# design.net
KiCad netlist of a schematic drawn in EasyEDA Pro
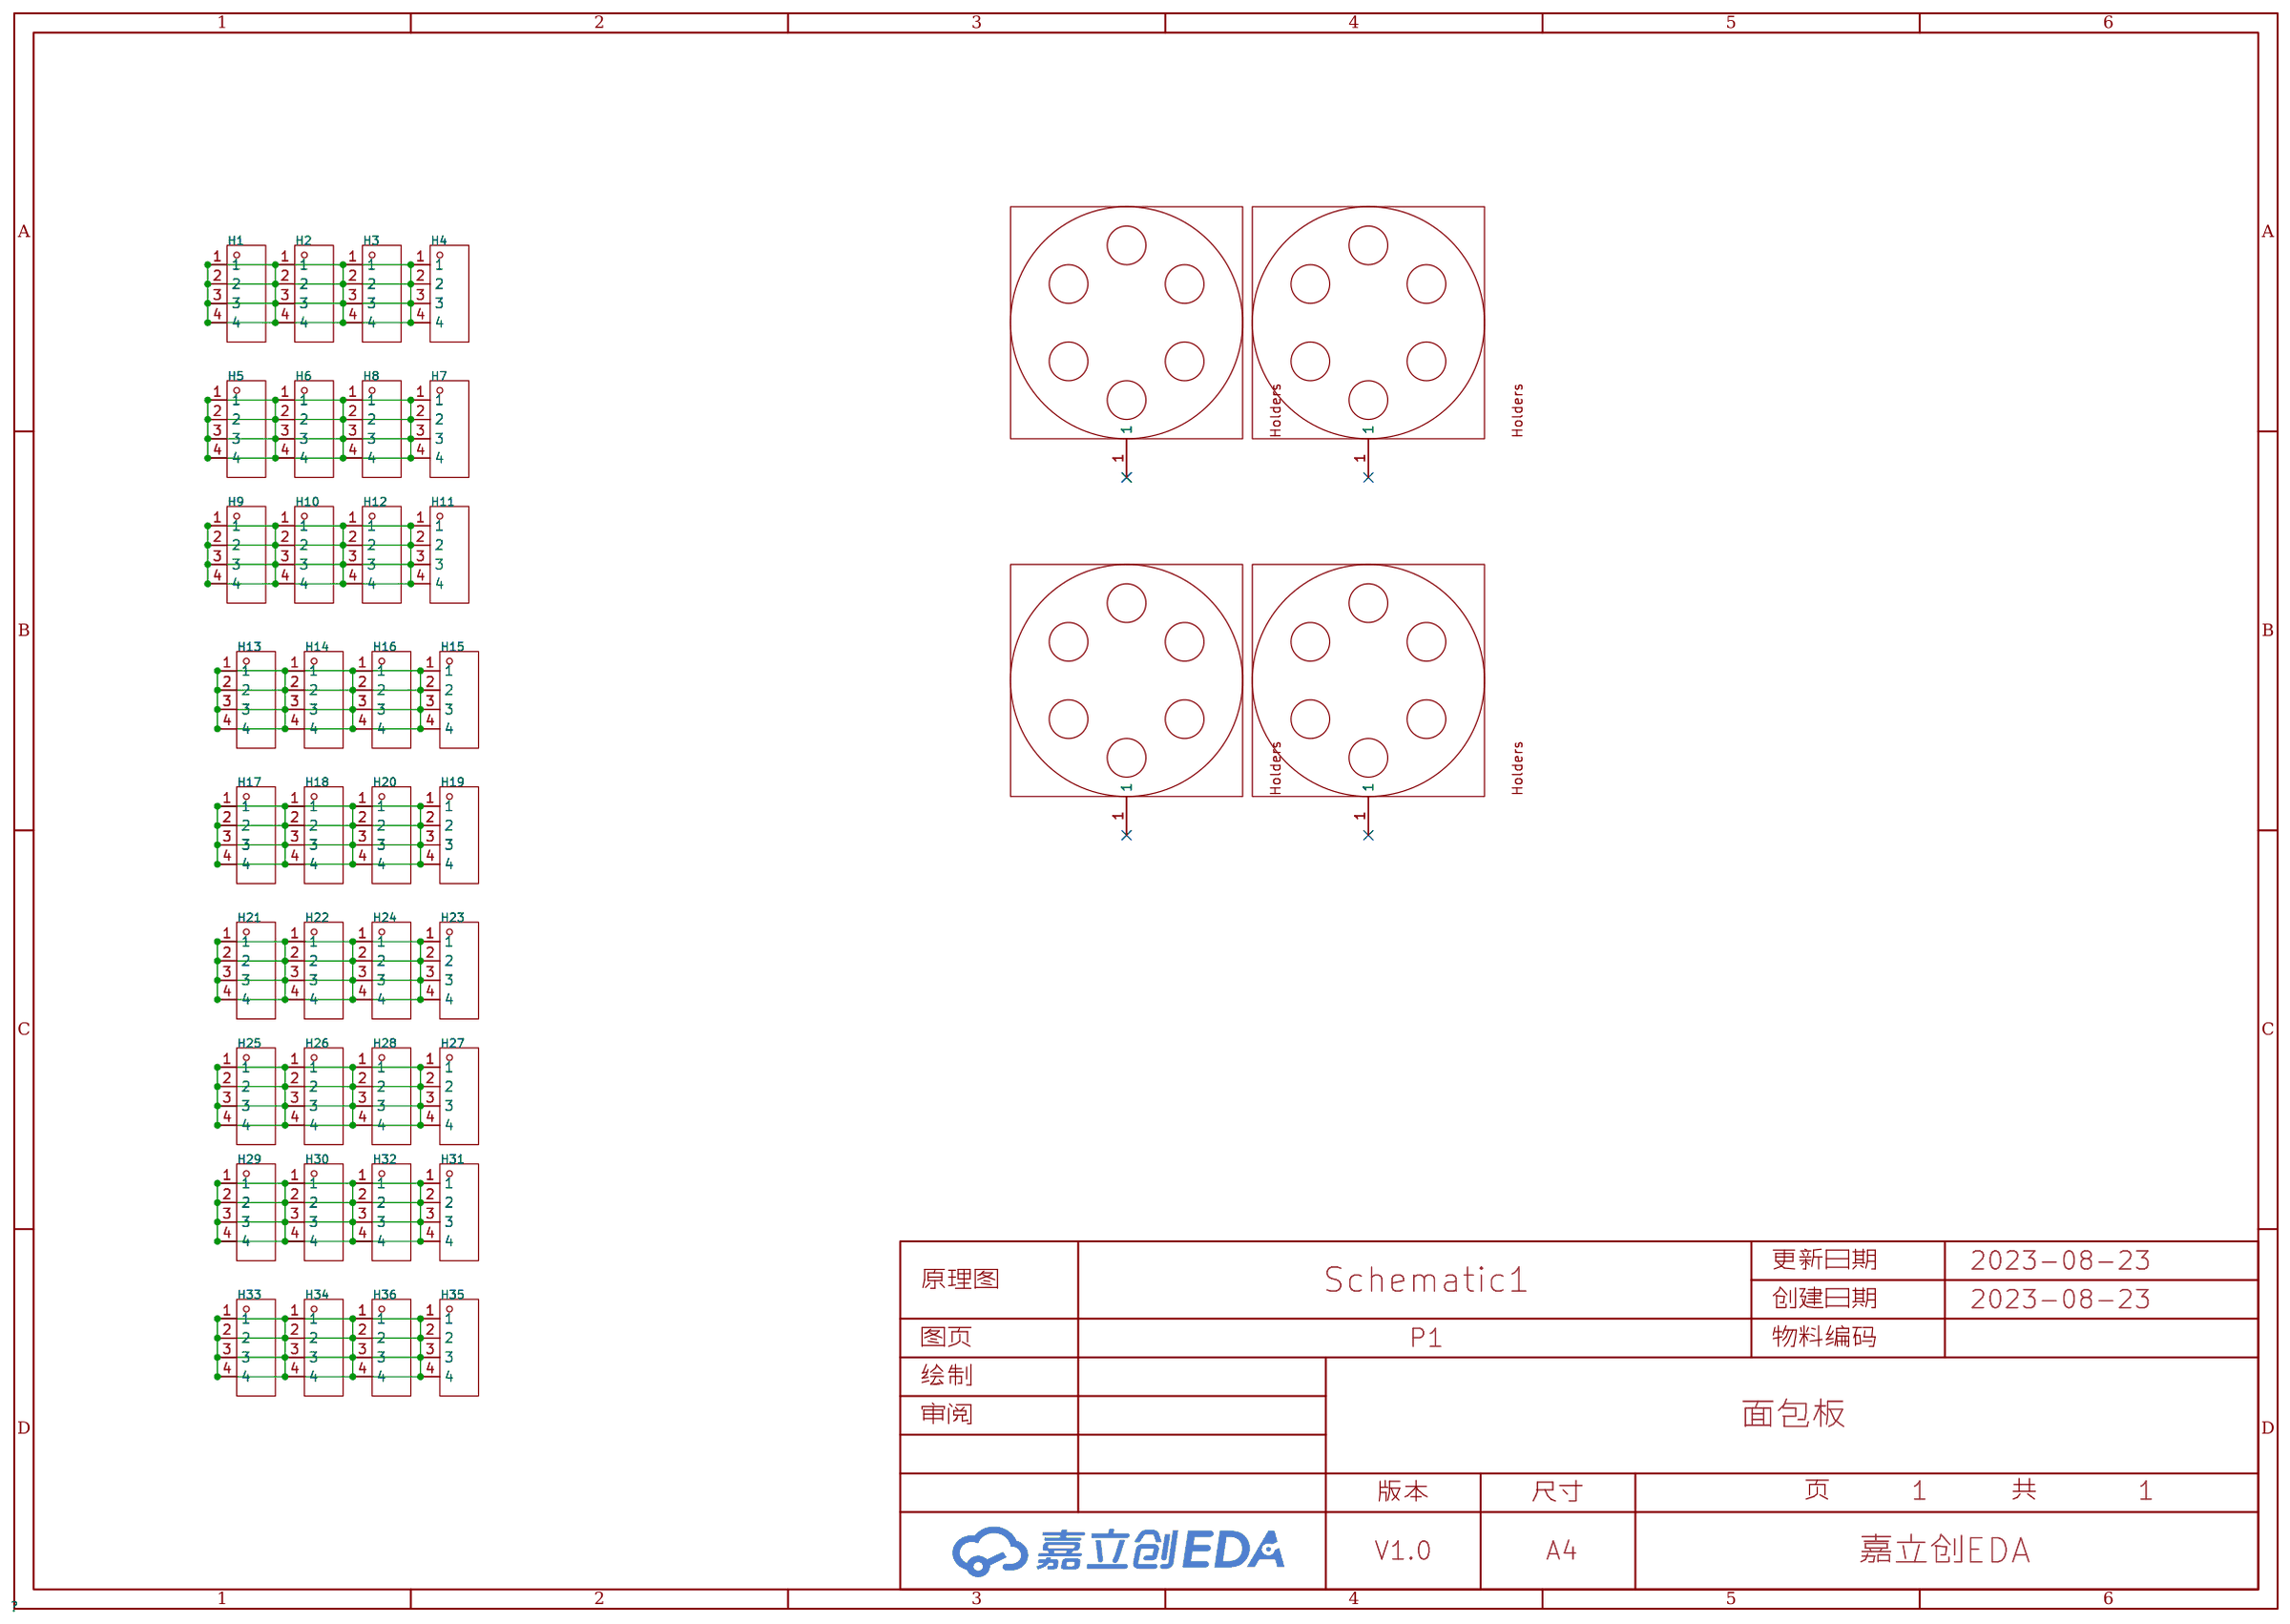
[diagram p0: schematic sheet]

(export (version "E")
  (design (tool "Eeschema 10.0.6"))
  (components
    (comp (ref "H1")
      (value "PZ254V-11-04P")
      (footprint "easyedapro:HDR-TH_4P-P2.54-V-M")
      (fields (field (name "Manufacturer") "XFCN(兴飞)"))
      (libsource (lib "easyedapro") (part "PZ254V-11-04P_C2691448"))
    )
    (comp (ref "H2")
      (value "PZ254V-11-04P")
      (footprint "easyedapro:HDR-TH_4P-P2.54-V-M")
      (fields (field (name "Manufacturer") "XFCN(兴飞)"))
      (libsource (lib "easyedapro") (part "PZ254V-11-04P_C2691448"))
    )
    (comp (ref "H3")
      (value "PZ254V-11-04P")
      (footprint "easyedapro:HDR-TH_4P-P2.54-V-M")
      (fields (field (name "Manufacturer") "XFCN(兴飞)"))
      (libsource (lib "easyedapro") (part "PZ254V-11-04P_C2691448"))
    )
    (comp (ref "H4")
      (value "PZ254V-11-04P")
      (footprint "easyedapro:HDR-TH_4P-P2.54-V-M")
      (fields (field (name "Manufacturer") "XFCN(兴飞)"))
      (libsource (lib "easyedapro") (part "PZ254V-11-04P_C2691448"))
    )
    (comp (ref "H5")
      (value "PZ254V-11-04P")
      (footprint "easyedapro:HDR-TH_4P-P2.54-V-M")
      (fields (field (name "Manufacturer") "XFCN(兴飞)"))
      (libsource (lib "easyedapro") (part "PZ254V-11-04P_C2691448"))
    )
    (comp (ref "H6")
      (value "PZ254V-11-04P")
      (footprint "easyedapro:HDR-TH_4P-P2.54-V-M")
      (fields (field (name "Manufacturer") "XFCN(兴飞)"))
      (libsource (lib "easyedapro") (part "PZ254V-11-04P_C2691448"))
    )
    (comp (ref "H7")
      (value "PZ254V-11-04P")
      (footprint "easyedapro:HDR-TH_4P-P2.54-V-M")
      (fields (field (name "Manufacturer") "XFCN(兴飞)"))
      (libsource (lib "easyedapro") (part "PZ254V-11-04P_C2691448"))
    )
    (comp (ref "H8")
      (value "PZ254V-11-04P")
      (footprint "easyedapro:HDR-TH_4P-P2.54-V-M")
      (fields (field (name "Manufacturer") "XFCN(兴飞)"))
      (libsource (lib "easyedapro") (part "PZ254V-11-04P_C2691448"))
    )
    (comp (ref "H9")
      (value "PZ254V-11-04P")
      (footprint "easyedapro:HDR-TH_4P-P2.54-V-M")
      (fields (field (name "Manufacturer") "XFCN(兴飞)"))
      (libsource (lib "easyedapro") (part "PZ254V-11-04P_C2691448"))
    )
    (comp (ref "H10")
      (value "PZ254V-11-04P")
      (footprint "easyedapro:HDR-TH_4P-P2.54-V-M")
      (fields (field (name "Manufacturer") "XFCN(兴飞)"))
      (libsource (lib "easyedapro") (part "PZ254V-11-04P_C2691448"))
    )
    (comp (ref "H11")
      (value "PZ254V-11-04P")
      (footprint "easyedapro:HDR-TH_4P-P2.54-V-M")
      (fields (field (name "Manufacturer") "XFCN(兴飞)"))
      (libsource (lib "easyedapro") (part "PZ254V-11-04P_C2691448"))
    )
    (comp (ref "H12")
      (value "PZ254V-11-04P")
      (footprint "easyedapro:HDR-TH_4P-P2.54-V-M")
      (fields (field (name "Manufacturer") "XFCN(兴飞)"))
      (libsource (lib "easyedapro") (part "PZ254V-11-04P_C2691448"))
    )
    (comp (ref "H13")
      (value "PZ254V-11-04P")
      (footprint "easyedapro:HDR-TH_4P-P2.54-V-M")
      (fields (field (name "Manufacturer") "XFCN(兴飞)"))
      (libsource (lib "easyedapro") (part "PZ254V-11-04P_C2691448"))
    )
    (comp (ref "H14")
      (value "PZ254V-11-04P")
      (footprint "easyedapro:HDR-TH_4P-P2.54-V-M")
      (fields (field (name "Manufacturer") "XFCN(兴飞)"))
      (libsource (lib "easyedapro") (part "PZ254V-11-04P_C2691448"))
    )
    (comp (ref "H15")
      (value "PZ254V-11-04P")
      (footprint "easyedapro:HDR-TH_4P-P2.54-V-M")
      (fields (field (name "Manufacturer") "XFCN(兴飞)"))
      (libsource (lib "easyedapro") (part "PZ254V-11-04P_C2691448"))
    )
    (comp (ref "H16")
      (value "PZ254V-11-04P")
      (footprint "easyedapro:HDR-TH_4P-P2.54-V-M")
      (fields (field (name "Manufacturer") "XFCN(兴飞)"))
      (libsource (lib "easyedapro") (part "PZ254V-11-04P_C2691448"))
    )
    (comp (ref "H17")
      (value "PZ254V-11-04P")
      (footprint "easyedapro:HDR-TH_4P-P2.54-V-M")
      (fields (field (name "Manufacturer") "XFCN(兴飞)"))
      (libsource (lib "easyedapro") (part "PZ254V-11-04P_C2691448"))
    )
    (comp (ref "H18")
      (value "PZ254V-11-04P")
      (footprint "easyedapro:HDR-TH_4P-P2.54-V-M")
      (fields (field (name "Manufacturer") "XFCN(兴飞)"))
      (libsource (lib "easyedapro") (part "PZ254V-11-04P_C2691448"))
    )
    (comp (ref "H19")
      (value "PZ254V-11-04P")
      (footprint "easyedapro:HDR-TH_4P-P2.54-V-M")
      (fields (field (name "Manufacturer") "XFCN(兴飞)"))
      (libsource (lib "easyedapro") (part "PZ254V-11-04P_C2691448"))
    )
    (comp (ref "H20")
      (value "PZ254V-11-04P")
      (footprint "easyedapro:HDR-TH_4P-P2.54-V-M")
      (fields (field (name "Manufacturer") "XFCN(兴飞)"))
      (libsource (lib "easyedapro") (part "PZ254V-11-04P_C2691448"))
    )
    (comp (ref "H21")
      (value "PZ254V-11-04P")
      (footprint "easyedapro:HDR-TH_4P-P2.54-V-M")
      (fields (field (name "Manufacturer") "XFCN(兴飞)"))
      (libsource (lib "easyedapro") (part "PZ254V-11-04P_C2691448"))
    )
    (comp (ref "H22")
      (value "PZ254V-11-04P")
      (footprint "easyedapro:HDR-TH_4P-P2.54-V-M")
      (fields (field (name "Manufacturer") "XFCN(兴飞)"))
      (libsource (lib "easyedapro") (part "PZ254V-11-04P_C2691448"))
    )
    (comp (ref "H23")
      (value "PZ254V-11-04P")
      (footprint "easyedapro:HDR-TH_4P-P2.54-V-M")
      (fields (field (name "Manufacturer") "XFCN(兴飞)"))
      (libsource (lib "easyedapro") (part "PZ254V-11-04P_C2691448"))
    )
    (comp (ref "H24")
      (value "PZ254V-11-04P")
      (footprint "easyedapro:HDR-TH_4P-P2.54-V-M")
      (fields (field (name "Manufacturer") "XFCN(兴飞)"))
      (libsource (lib "easyedapro") (part "PZ254V-11-04P_C2691448"))
    )
    (comp (ref "H25")
      (value "PZ254V-11-04P")
      (footprint "easyedapro:HDR-TH_4P-P2.54-V-M")
      (fields (field (name "Manufacturer") "XFCN(兴飞)"))
      (libsource (lib "easyedapro") (part "PZ254V-11-04P_C2691448"))
    )
    (comp (ref "H26")
      (value "PZ254V-11-04P")
      (footprint "easyedapro:HDR-TH_4P-P2.54-V-M")
      (fields (field (name "Manufacturer") "XFCN(兴飞)"))
      (libsource (lib "easyedapro") (part "PZ254V-11-04P_C2691448"))
    )
    (comp (ref "H27")
      (value "PZ254V-11-04P")
      (footprint "easyedapro:HDR-TH_4P-P2.54-V-M")
      (fields (field (name "Manufacturer") "XFCN(兴飞)"))
      (libsource (lib "easyedapro") (part "PZ254V-11-04P_C2691448"))
    )
    (comp (ref "H28")
      (value "PZ254V-11-04P")
      (footprint "easyedapro:HDR-TH_4P-P2.54-V-M")
      (fields (field (name "Manufacturer") "XFCN(兴飞)"))
      (libsource (lib "easyedapro") (part "PZ254V-11-04P_C2691448"))
    )
    (comp (ref "H29")
      (value "PZ254V-11-04P")
      (footprint "easyedapro:HDR-TH_4P-P2.54-V-M")
      (fields (field (name "Manufacturer") "XFCN(兴飞)"))
      (libsource (lib "easyedapro") (part "PZ254V-11-04P_C2691448"))
    )
    (comp (ref "H30")
      (value "PZ254V-11-04P")
      (footprint "easyedapro:HDR-TH_4P-P2.54-V-M")
      (fields (field (name "Manufacturer") "XFCN(兴飞)"))
      (libsource (lib "easyedapro") (part "PZ254V-11-04P_C2691448"))
    )
    (comp (ref "H31")
      (value "PZ254V-11-04P")
      (footprint "easyedapro:HDR-TH_4P-P2.54-V-M")
      (fields (field (name "Manufacturer") "XFCN(兴飞)"))
      (libsource (lib "easyedapro") (part "PZ254V-11-04P_C2691448"))
    )
    (comp (ref "H32")
      (value "PZ254V-11-04P")
      (footprint "easyedapro:HDR-TH_4P-P2.54-V-M")
      (fields (field (name "Manufacturer") "XFCN(兴飞)"))
      (libsource (lib "easyedapro") (part "PZ254V-11-04P_C2691448"))
    )
    (comp (ref "H33")
      (value "PZ254V-11-04P")
      (footprint "easyedapro:HDR-TH_4P-P2.54-V-M")
      (fields (field (name "Manufacturer") "XFCN(兴飞)"))
      (libsource (lib "easyedapro") (part "PZ254V-11-04P_C2691448"))
    )
    (comp (ref "H34")
      (value "PZ254V-11-04P")
      (footprint "easyedapro:HDR-TH_4P-P2.54-V-M")
      (fields (field (name "Manufacturer") "XFCN(兴飞)"))
      (libsource (lib "easyedapro") (part "PZ254V-11-04P_C2691448"))
    )
    (comp (ref "H35")
      (value "PZ254V-11-04P")
      (footprint "easyedapro:HDR-TH_4P-P2.54-V-M")
      (fields (field (name "Manufacturer") "XFCN(兴飞)"))
      (libsource (lib "easyedapro") (part "PZ254V-11-04P_C2691448"))
    )
    (comp (ref "H36")
      (value "PZ254V-11-04P")
      (footprint "easyedapro:HDR-TH_4P-P2.54-V-M")
      (fields (field (name "Manufacturer") "XFCN(兴飞)"))
      (libsource (lib "easyedapro") (part "PZ254V-11-04P_C2691448"))
    )
    (comp (ref "J1")
      (value "~")
      (footprint "easyedapro:DEMO板安装孔")
      (libsource (lib "easyedapro") (part "螺孔_3.1X6MM"))
    )
    (comp (ref "J2")
      (value "~")
      (footprint "easyedapro:DEMO板安装孔")
      (libsource (lib "easyedapro") (part "螺孔_3.1X6MM"))
    )
    (comp (ref "J3")
      (value "~")
      (footprint "easyedapro:DEMO板安装孔")
      (libsource (lib "easyedapro") (part "螺孔_3.1X6MM"))
    )
    (comp (ref "J4")
      (value "~")
      (footprint "easyedapro:DEMO板安装孔")
      (libsource (lib "easyedapro") (part "螺孔_3.1X6MM"))
    )
  )
  (nets
    (net (code "1") (name "Net-(H1-Pad1)") (class "Default")
      (node (ref "H1") (pin "1") (pinfunction "1_1") (pintype "input"))
      (node (ref "H1") (pin "2") (pinfunction "2_2") (pintype "input"))
      (node (ref "H1") (pin "3") (pinfunction "3_3") (pintype "input"))
      (node (ref "H1") (pin "4") (pinfunction "4_4") (pintype "input"))
      (node (ref "H2") (pin "1") (pinfunction "1_1") (pintype "input"))
      (node (ref "H2") (pin "2") (pinfunction "2_2") (pintype "input"))
      (node (ref "H2") (pin "3") (pinfunction "3_3") (pintype "input"))
      (node (ref "H2") (pin "4") (pinfunction "4_4") (pintype "input"))
      (node (ref "H3") (pin "1") (pinfunction "1_1") (pintype "input"))
      (node (ref "H3") (pin "2") (pinfunction "2_2") (pintype "input"))
      (node (ref "H3") (pin "3") (pinfunction "3_3") (pintype "input"))
      (node (ref "H3") (pin "4") (pinfunction "4_4") (pintype "input"))
      (node (ref "H4") (pin "1") (pinfunction "1_1") (pintype "input"))
      (node (ref "H4") (pin "2") (pinfunction "2_2") (pintype "input"))
      (node (ref "H4") (pin "3") (pinfunction "3_3") (pintype "input"))
      (node (ref "H4") (pin "4") (pinfunction "4_4") (pintype "input"))
    )
    (net (code "2") (name "Net-(H5-Pad1)") (class "Default")
      (node (ref "H5") (pin "1") (pinfunction "1_1") (pintype "input"))
      (node (ref "H5") (pin "2") (pinfunction "2_2") (pintype "input"))
      (node (ref "H5") (pin "3") (pinfunction "3_3") (pintype "input"))
      (node (ref "H5") (pin "4") (pinfunction "4_4") (pintype "input"))
      (node (ref "H6") (pin "1") (pinfunction "1_1") (pintype "input"))
      (node (ref "H6") (pin "2") (pinfunction "2_2") (pintype "input"))
      (node (ref "H6") (pin "3") (pinfunction "3_3") (pintype "input"))
      (node (ref "H6") (pin "4") (pinfunction "4_4") (pintype "input"))
      (node (ref "H7") (pin "1") (pinfunction "1_1") (pintype "input"))
      (node (ref "H7") (pin "2") (pinfunction "2_2") (pintype "input"))
      (node (ref "H7") (pin "3") (pinfunction "3_3") (pintype "input"))
      (node (ref "H7") (pin "4") (pinfunction "4_4") (pintype "input"))
      (node (ref "H8") (pin "1") (pinfunction "1_1") (pintype "input"))
      (node (ref "H8") (pin "2") (pinfunction "2_2") (pintype "input"))
      (node (ref "H8") (pin "3") (pinfunction "3_3") (pintype "input"))
      (node (ref "H8") (pin "4") (pinfunction "4_4") (pintype "input"))
    )
    (net (code "3") (name "Net-(H10-Pad1)") (class "Default")
      (node (ref "H10") (pin "1") (pinfunction "1_1") (pintype "input"))
      (node (ref "H10") (pin "2") (pinfunction "2_2") (pintype "input"))
      (node (ref "H10") (pin "3") (pinfunction "3_3") (pintype "input"))
      (node (ref "H10") (pin "4") (pinfunction "4_4") (pintype "input"))
      (node (ref "H11") (pin "1") (pinfunction "1_1") (pintype "input"))
      (node (ref "H11") (pin "2") (pinfunction "2_2") (pintype "input"))
      (node (ref "H11") (pin "3") (pinfunction "3_3") (pintype "input"))
      (node (ref "H11") (pin "4") (pinfunction "4_4") (pintype "input"))
      (node (ref "H12") (pin "1") (pinfunction "1_1") (pintype "input"))
      (node (ref "H12") (pin "2") (pinfunction "2_2") (pintype "input"))
      (node (ref "H12") (pin "3") (pinfunction "3_3") (pintype "input"))
      (node (ref "H12") (pin "4") (pinfunction "4_4") (pintype "input"))
      (node (ref "H9") (pin "1") (pinfunction "1_1") (pintype "input"))
      (node (ref "H9") (pin "2") (pinfunction "2_2") (pintype "input"))
      (node (ref "H9") (pin "3") (pinfunction "3_3") (pintype "input"))
      (node (ref "H9") (pin "4") (pinfunction "4_4") (pintype "input"))
    )
    (net (code "4") (name "Net-(H13-Pad1)") (class "Default")
      (node (ref "H13") (pin "1") (pinfunction "1_1") (pintype "input"))
      (node (ref "H13") (pin "2") (pinfunction "2_2") (pintype "input"))
      (node (ref "H13") (pin "3") (pinfunction "3_3") (pintype "input"))
      (node (ref "H13") (pin "4") (pinfunction "4_4") (pintype "input"))
      (node (ref "H14") (pin "1") (pinfunction "1_1") (pintype "input"))
      (node (ref "H14") (pin "2") (pinfunction "2_2") (pintype "input"))
      (node (ref "H14") (pin "3") (pinfunction "3_3") (pintype "input"))
      (node (ref "H14") (pin "4") (pinfunction "4_4") (pintype "input"))
      (node (ref "H15") (pin "1") (pinfunction "1_1") (pintype "input"))
      (node (ref "H15") (pin "2") (pinfunction "2_2") (pintype "input"))
      (node (ref "H15") (pin "3") (pinfunction "3_3") (pintype "input"))
      (node (ref "H15") (pin "4") (pinfunction "4_4") (pintype "input"))
      (node (ref "H16") (pin "1") (pinfunction "1_1") (pintype "input"))
      (node (ref "H16") (pin "2") (pinfunction "2_2") (pintype "input"))
      (node (ref "H16") (pin "3") (pinfunction "3_3") (pintype "input"))
      (node (ref "H16") (pin "4") (pinfunction "4_4") (pintype "input"))
    )
    (net (code "5") (name "Net-(H17-Pad1)") (class "Default")
      (node (ref "H17") (pin "1") (pinfunction "1_1") (pintype "input"))
      (node (ref "H17") (pin "2") (pinfunction "2_2") (pintype "input"))
      (node (ref "H17") (pin "3") (pinfunction "3_3") (pintype "input"))
      (node (ref "H17") (pin "4") (pinfunction "4_4") (pintype "input"))
      (node (ref "H18") (pin "1") (pinfunction "1_1") (pintype "input"))
      (node (ref "H18") (pin "2") (pinfunction "2_2") (pintype "input"))
      (node (ref "H18") (pin "3") (pinfunction "3_3") (pintype "input"))
      (node (ref "H18") (pin "4") (pinfunction "4_4") (pintype "input"))
      (node (ref "H19") (pin "1") (pinfunction "1_1") (pintype "input"))
      (node (ref "H19") (pin "2") (pinfunction "2_2") (pintype "input"))
      (node (ref "H19") (pin "3") (pinfunction "3_3") (pintype "input"))
      (node (ref "H19") (pin "4") (pinfunction "4_4") (pintype "input"))
      (node (ref "H20") (pin "1") (pinfunction "1_1") (pintype "input"))
      (node (ref "H20") (pin "2") (pinfunction "2_2") (pintype "input"))
      (node (ref "H20") (pin "3") (pinfunction "3_3") (pintype "input"))
      (node (ref "H20") (pin "4") (pinfunction "4_4") (pintype "input"))
    )
    (net (code "6") (name "Net-(H21-Pad1)") (class "Default")
      (node (ref "H21") (pin "1") (pinfunction "1_1") (pintype "input"))
      (node (ref "H21") (pin "2") (pinfunction "2_2") (pintype "input"))
      (node (ref "H21") (pin "3") (pinfunction "3_3") (pintype "input"))
      (node (ref "H21") (pin "4") (pinfunction "4_4") (pintype "input"))
      (node (ref "H22") (pin "1") (pinfunction "1_1") (pintype "input"))
      (node (ref "H22") (pin "2") (pinfunction "2_2") (pintype "input"))
      (node (ref "H22") (pin "3") (pinfunction "3_3") (pintype "input"))
      (node (ref "H22") (pin "4") (pinfunction "4_4") (pintype "input"))
      (node (ref "H23") (pin "1") (pinfunction "1_1") (pintype "input"))
      (node (ref "H23") (pin "2") (pinfunction "2_2") (pintype "input"))
      (node (ref "H23") (pin "3") (pinfunction "3_3") (pintype "input"))
      (node (ref "H23") (pin "4") (pinfunction "4_4") (pintype "input"))
      (node (ref "H24") (pin "1") (pinfunction "1_1") (pintype "input"))
      (node (ref "H24") (pin "2") (pinfunction "2_2") (pintype "input"))
      (node (ref "H24") (pin "3") (pinfunction "3_3") (pintype "input"))
      (node (ref "H24") (pin "4") (pinfunction "4_4") (pintype "input"))
    )
    (net (code "7") (name "Net-(H25-Pad1)") (class "Default")
      (node (ref "H25") (pin "1") (pinfunction "1_1") (pintype "input"))
      (node (ref "H25") (pin "2") (pinfunction "2_2") (pintype "input"))
      (node (ref "H25") (pin "3") (pinfunction "3_3") (pintype "input"))
      (node (ref "H25") (pin "4") (pinfunction "4_4") (pintype "input"))
      (node (ref "H26") (pin "1") (pinfunction "1_1") (pintype "input"))
      (node (ref "H26") (pin "2") (pinfunction "2_2") (pintype "input"))
      (node (ref "H26") (pin "3") (pinfunction "3_3") (pintype "input"))
      (node (ref "H26") (pin "4") (pinfunction "4_4") (pintype "input"))
      (node (ref "H27") (pin "1") (pinfunction "1_1") (pintype "input"))
      (node (ref "H27") (pin "2") (pinfunction "2_2") (pintype "input"))
      (node (ref "H27") (pin "3") (pinfunction "3_3") (pintype "input"))
      (node (ref "H27") (pin "4") (pinfunction "4_4") (pintype "input"))
      (node (ref "H28") (pin "1") (pinfunction "1_1") (pintype "input"))
      (node (ref "H28") (pin "2") (pinfunction "2_2") (pintype "input"))
      (node (ref "H28") (pin "3") (pinfunction "3_3") (pintype "input"))
      (node (ref "H28") (pin "4") (pinfunction "4_4") (pintype "input"))
    )
    (net (code "8") (name "Net-(H29-Pad1)") (class "Default")
      (node (ref "H29") (pin "1") (pinfunction "1_1") (pintype "input"))
      (node (ref "H29") (pin "2") (pinfunction "2_2") (pintype "input"))
      (node (ref "H29") (pin "3") (pinfunction "3_3") (pintype "input"))
      (node (ref "H29") (pin "4") (pinfunction "4_4") (pintype "input"))
      (node (ref "H30") (pin "1") (pinfunction "1_1") (pintype "input"))
      (node (ref "H30") (pin "2") (pinfunction "2_2") (pintype "input"))
      (node (ref "H30") (pin "3") (pinfunction "3_3") (pintype "input"))
      (node (ref "H30") (pin "4") (pinfunction "4_4") (pintype "input"))
      (node (ref "H31") (pin "1") (pinfunction "1_1") (pintype "input"))
      (node (ref "H31") (pin "2") (pinfunction "2_2") (pintype "input"))
      (node (ref "H31") (pin "3") (pinfunction "3_3") (pintype "input"))
      (node (ref "H31") (pin "4") (pinfunction "4_4") (pintype "input"))
      (node (ref "H32") (pin "1") (pinfunction "1_1") (pintype "input"))
      (node (ref "H32") (pin "2") (pinfunction "2_2") (pintype "input"))
      (node (ref "H32") (pin "3") (pinfunction "3_3") (pintype "input"))
      (node (ref "H32") (pin "4") (pinfunction "4_4") (pintype "input"))
    )
    (net (code "9") (name "Net-(H33-Pad1)") (class "Default")
      (node (ref "H33") (pin "1") (pinfunction "1_1") (pintype "input"))
      (node (ref "H33") (pin "2") (pinfunction "2_2") (pintype "input"))
      (node (ref "H33") (pin "3") (pinfunction "3_3") (pintype "input"))
      (node (ref "H33") (pin "4") (pinfunction "4_4") (pintype "input"))
      (node (ref "H34") (pin "1") (pinfunction "1_1") (pintype "input"))
      (node (ref "H34") (pin "2") (pinfunction "2_2") (pintype "input"))
      (node (ref "H34") (pin "3") (pinfunction "3_3") (pintype "input"))
      (node (ref "H34") (pin "4") (pinfunction "4_4") (pintype "input"))
      (node (ref "H35") (pin "1") (pinfunction "1_1") (pintype "input"))
      (node (ref "H35") (pin "2") (pinfunction "2_2") (pintype "input"))
      (node (ref "H35") (pin "3") (pinfunction "3_3") (pintype "input"))
      (node (ref "H35") (pin "4") (pinfunction "4_4") (pintype "input"))
      (node (ref "H36") (pin "1") (pinfunction "1_1") (pintype "input"))
      (node (ref "H36") (pin "2") (pinfunction "2_2") (pintype "input"))
      (node (ref "H36") (pin "3") (pinfunction "3_3") (pintype "input"))
      (node (ref "H36") (pin "4") (pinfunction "4_4") (pintype "input"))
    )
    (net (code "10") (name "unconnected-(J1-Pad1)") (class "Default")
      (node (ref "J1") (pin "1") (pinfunction "1_1") (pintype "input+no_connect"))
    )
    (net (code "11") (name "unconnected-(J2-Pad1)") (class "Default")
      (node (ref "J2") (pin "1") (pinfunction "1_1") (pintype "input+no_connect"))
    )
    (net (code "12") (name "unconnected-(J3-Pad1)") (class "Default")
      (node (ref "J3") (pin "1") (pinfunction "1_1") (pintype "input+no_connect"))
    )
    (net (code "13") (name "unconnected-(J4-Pad1)") (class "Default")
      (node (ref "J4") (pin "1") (pinfunction "1_1") (pintype "input+no_connect"))
    )
  )
)
